# ALA_BOARD.net
KiCad netlist of a schematic drawn in EAGLE
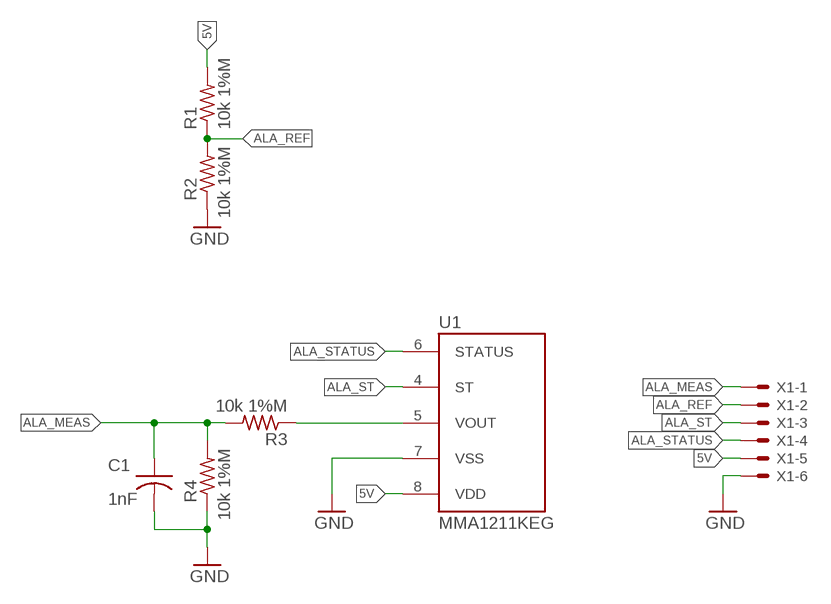
[diagram p0: schematic, sheet 1]

(export (version "E")
  (design (tool "Eeschema 10.0.6"))
  (components
    (comp (ref "C1")
      (value "1nF")
      (footprint "eagle-import:C0805")
      (libsource (lib "eagle-import") (part "C-USC0805"))
    )
    (comp (ref "R1")
      (value "10k 1%M")
      (footprint "eagle-import:R0805")
      (libsource (lib "eagle-import") (part "R-US_R0805"))
    )
    (comp (ref "R2")
      (value "10k 1%M")
      (footprint "eagle-import:R0805")
      (libsource (lib "eagle-import") (part "R-US_R0805"))
    )
    (comp (ref "R3")
      (value "10k 1%M")
      (footprint "eagle-import:R0805")
      (libsource (lib "eagle-import") (part "R-US_R0805"))
    )
    (comp (ref "R4")
      (value "10k 1%M")
      (footprint "eagle-import:R0805")
      (libsource (lib "eagle-import") (part "R-US_R0805"))
    )
    (comp (ref "U1")
      (value "MMA1211KEG")
      (footprint "eagle-import:SOIC127P1041X355-16N")
      (libsource (lib "eagle-import") (part "MMA1211KEG"))
    )
    (comp (ref "X1")
      (value "22-23-2061")
      (footprint "eagle-import:22-23-2061")
      (fields (field (name "MF") "MOLEX"))
      (libsource (lib "eagle-import") (part "22-23-2061"))
    )
  )
  (nets
    (net (code "1") (name "5V") (class "Default")
      (node (ref "R1") (pin "2") (pinfunction "2_2") (pintype "passive"))
      (node (ref "U1") (pin "8") (pinfunction "VDD_8") (pintype "bidirectional"))
      (node (ref "X1") (pin "5") (pinfunction "S_5") (pintype "passive"))
    )
    (net (code "2") (name "ALA_MEAS") (class "Default")
      (node (ref "C1") (pin "1") (pinfunction "1_1") (pintype "passive"))
      (node (ref "R3") (pin "2") (pinfunction "2_2") (pintype "passive"))
      (node (ref "R4") (pin "2") (pinfunction "2_2") (pintype "passive"))
      (node (ref "X1") (pin "1") (pinfunction "S_1") (pintype "passive"))
    )
    (net (code "3") (name "ALA_REF") (class "Default")
      (node (ref "R1") (pin "1") (pinfunction "1_1") (pintype "passive"))
      (node (ref "R2") (pin "2") (pinfunction "2_2") (pintype "passive"))
      (node (ref "X1") (pin "2") (pinfunction "S_2") (pintype "passive"))
    )
    (net (code "4") (name "ALA_ST") (class "Default")
      (node (ref "U1") (pin "4") (pinfunction "ST_4") (pintype "bidirectional"))
      (node (ref "X1") (pin "3") (pinfunction "S_3") (pintype "passive"))
    )
    (net (code "5") (name "ALA_STATUS") (class "Default")
      (node (ref "U1") (pin "6") (pinfunction "STATUS_6") (pintype "bidirectional"))
      (node (ref "X1") (pin "4") (pinfunction "S_4") (pintype "passive"))
    )
    (net (code "6") (name "GND") (class "Default")
      (node (ref "C1") (pin "2") (pinfunction "2_2") (pintype "passive"))
      (node (ref "R2") (pin "1") (pinfunction "1_1") (pintype "passive"))
      (node (ref "R4") (pin "1") (pinfunction "1_1") (pintype "passive"))
      (node (ref "U1") (pin "7") (pinfunction "VSS_7") (pintype "bidirectional"))
      (node (ref "X1") (pin "6") (pinfunction "S_6") (pintype "passive"))
    )
    (net (code "7") (name "Net-(U1-VOUT)") (class "Default")
      (node (ref "R3") (pin "1") (pinfunction "1_1") (pintype "passive"))
      (node (ref "U1") (pin "5") (pinfunction "VOUT_5") (pintype "bidirectional"))
    )
  )
)
